# tl494.net
KiCad netlist of a schematic drawn in EAGLE
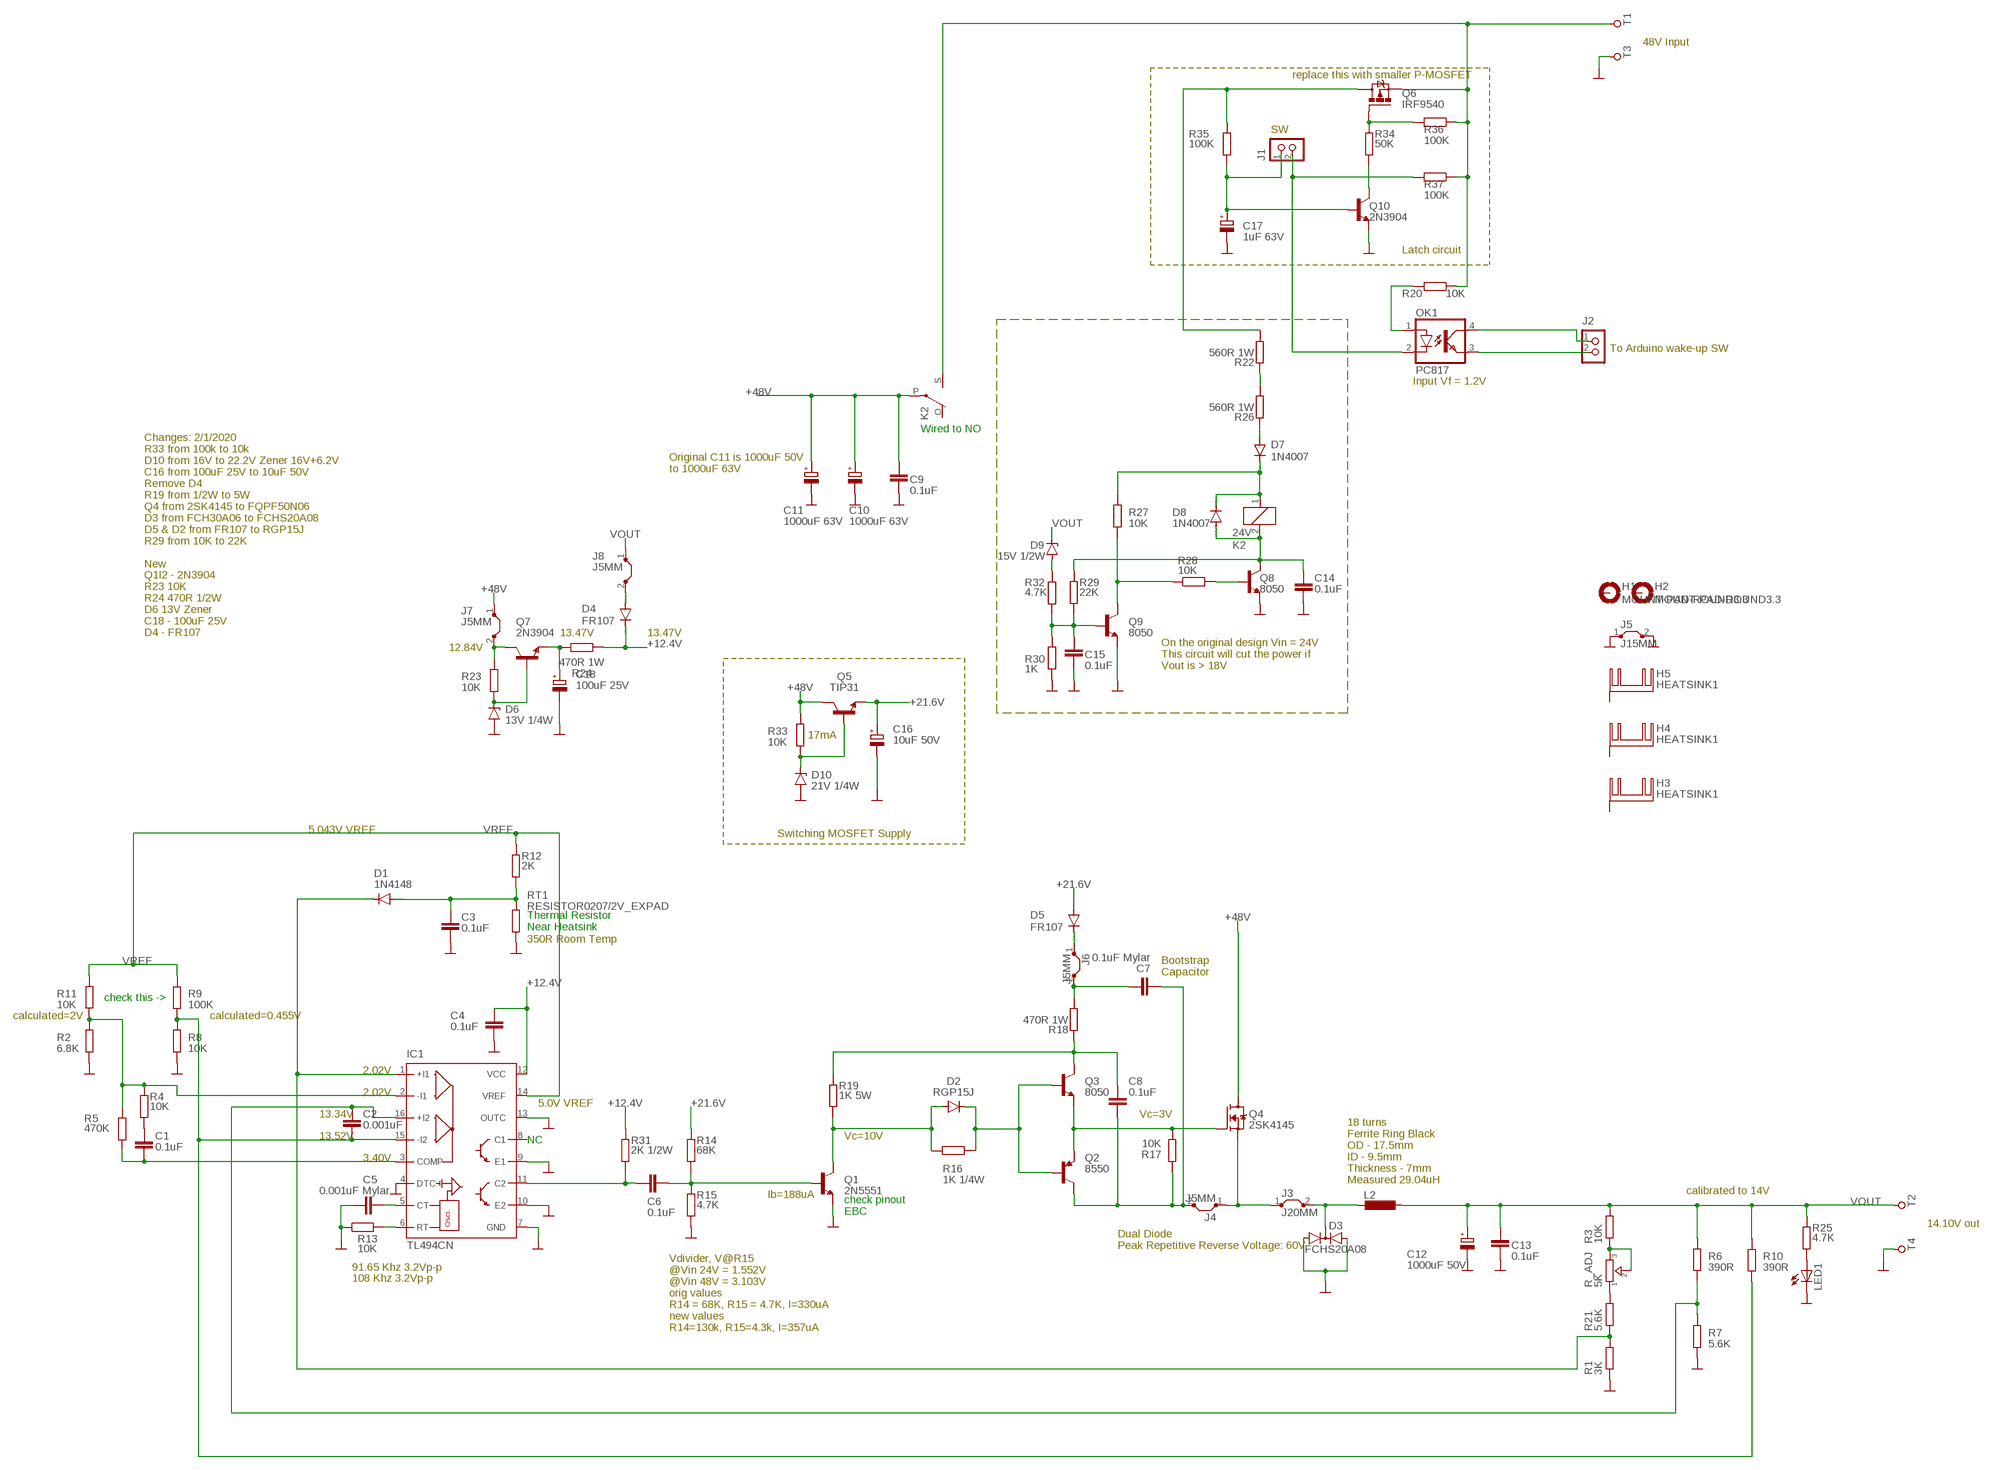
[diagram p0: schematic, sheet 1]

(export (version "E")
  (design (tool "Eeschema 10.0.6"))
  (components
    (comp (ref "C1")
      (value "0.1uF")
      (footprint "eagle-import:C050-024X044_EXPAD")
      (libsource (lib "eagle-import") (part "CAPACITORC050-024X044_EXPAD"))
    )
    (comp (ref "C2")
      (value "0.001uF")
      (footprint "eagle-import:C050-024X044_EXPAD")
      (libsource (lib "eagle-import") (part "CAPACITORC050-024X044_EXPAD"))
    )
    (comp (ref "C3")
      (value "0.1uF")
      (footprint "eagle-import:C050-024X044_EXPAD")
      (libsource (lib "eagle-import") (part "CAPACITORC050-024X044_EXPAD"))
    )
    (comp (ref "C4")
      (value "0.1uF")
      (footprint "eagle-import:C050-024X044_EXPAD")
      (libsource (lib "eagle-import") (part "CAPACITORC050-024X044_EXPAD"))
    )
    (comp (ref "C5")
      (value "0.001uF Mylar")
      (footprint "eagle-import:C050-024X044_EXPAD")
      (libsource (lib "eagle-import") (part "CAPACITORC050-024X044_EXPAD"))
    )
    (comp (ref "C6")
      (value "0.1uF")
      (footprint "eagle-import:C050-024X044_EXPAD")
      (libsource (lib "eagle-import") (part "CAPACITORC050-024X044_EXPAD"))
    )
    (comp (ref "C7")
      (value "0.1uF Mylar")
      (footprint "eagle-import:C050-050X075_EXPAD")
      (libsource (lib "eagle-import") (part "CAPACITORC050-050X075_EXPAD"))
    )
    (comp (ref "C8")
      (value "0.1uF")
      (footprint "eagle-import:C050-024X044_EXPAD")
      (libsource (lib "eagle-import") (part "CAPACITORC050-024X044_EXPAD"))
    )
    (comp (ref "C9")
      (value "0.1uF")
      (footprint "eagle-import:C050-024X044_EXPAD")
      (libsource (lib "eagle-import") (part "CAPACITORC050-024X044_EXPAD"))
    )
    (comp (ref "C10")
      (value "1000uF 63V")
      (footprint "eagle-import:E7,5-18")
      (libsource (lib "eagle-import") (part "CPOL-EUE7.5-18"))
    )
    (comp (ref "C11")
      (value "1000uF 63V")
      (footprint "eagle-import:E7,5-18")
      (libsource (lib "eagle-import") (part "CPOL-EUE7.5-18"))
    )
    (comp (ref "C12")
      (value "1000uF 50V")
      (footprint "eagle-import:E5-13")
      (libsource (lib "eagle-import") (part "CPOL-EUE5-13"))
    )
    (comp (ref "C13")
      (value "0.1uF")
      (footprint "eagle-import:C050-024X044_EXPAD")
      (libsource (lib "eagle-import") (part "CAPACITORC050-024X044_EXPAD"))
    )
    (comp (ref "C14")
      (value "0.1uF")
      (footprint "eagle-import:C050-024X044_EXPAD")
      (libsource (lib "eagle-import") (part "CAPACITORC050-024X044_EXPAD"))
    )
    (comp (ref "C15")
      (value "0.1uF")
      (footprint "eagle-import:C050-024X044_EXPAD")
      (libsource (lib "eagle-import") (part "CAPACITORC050-024X044_EXPAD"))
    )
    (comp (ref "C16")
      (value "10uF 50V")
      (footprint "eagle-import:E2,5-7_EXPAD")
      (libsource (lib "eagle-import") (part "CAPACITOR-POLE2,5-7_EXPAD"))
    )
    (comp (ref "C17")
      (value "1uF 63V")
      (footprint "eagle-import:E2-5_EXPAD")
      (libsource (lib "eagle-import") (part "CAPACITOR-POLE2,5_EXPAD"))
    )
    (comp (ref "C18")
      (value "100uF 25V")
      (footprint "eagle-import:E2,5-7_EXPAD")
      (libsource (lib "eagle-import") (part "CAPACITOR-POLE2,5-7_EXPAD"))
    )
    (comp (ref "D1")
      (value "1N4148")
      (footprint "eagle-import:DO35-10")
      (libsource (lib "eagle-import") (part "1N4148DO35-10"))
    )
    (comp (ref "D2")
      (value "RGP15J")
      (footprint "eagle-import:DO41-10")
      (libsource (lib "eagle-import") (part "1N4933"))
    )
    (comp (ref "D3")
      (value "FCHS20A08")
      (footprint "eagle-import:TO220ABS")
      (libsource (lib "eagle-import") (part "DIODE-2AC|CATO220V"))
    )
    (comp (ref "D4")
      (value "FR107")
      (footprint "eagle-import:DO41-10")
      (libsource (lib "eagle-import") (part "1N4933"))
    )
    (comp (ref "D5")
      (value "FR107")
      (footprint "eagle-import:DO41-10")
      (libsource (lib "eagle-import") (part "1N4933"))
    )
    (comp (ref "D6")
      (value "13V 1/4W")
      (footprint "eagle-import:DO34Z7")
      (libsource (lib "eagle-import") (part "BZV10"))
    )
    (comp (ref "D7")
      (value "1N4007")
      (footprint "eagle-import:DO41-10")
      (libsource (lib "eagle-import") (part "1N4933"))
    )
    (comp (ref "D8")
      (value "1N4007")
      (footprint "eagle-import:DO41-10")
      (libsource (lib "eagle-import") (part "1N4933"))
    )
    (comp (ref "D9")
      (value "15V 1/2W")
      (footprint "eagle-import:DO34Z7")
      (libsource (lib "eagle-import") (part "BZV10"))
    )
    (comp (ref "D10")
      (value "21V 1/4W")
      (footprint "eagle-import:DO34Z7")
      (libsource (lib "eagle-import") (part "BZV10"))
    )
    (comp (ref "H1")
      (value "MOUNT-PAD-ROUND3.3")
      (footprint "eagle-import:3,3-PAD")
      (libsource (lib "eagle-import") (part "MOUNT-PAD-ROUND3.3"))
    )
    (comp (ref "H2")
      (value "MOUNT-PAD-ROUND3.3")
      (footprint "eagle-import:3,3-PAD")
      (libsource (lib "eagle-import") (part "MOUNT-PAD-ROUND3.3"))
    )
    (comp (ref "H3")
      (value "HEATSINK1")
      (footprint "eagle-import:TO-220_HEATSINK1")
      (libsource (lib "eagle-import") (part "HEATSINK1"))
    )
    (comp (ref "H4")
      (value "HEATSINK1")
      (footprint "eagle-import:TO-220_HEATSINK1")
      (libsource (lib "eagle-import") (part "HEATSINK1"))
    )
    (comp (ref "H5")
      (value "HEATSINK1")
      (footprint "eagle-import:TO-220_HEATSINK1")
      (libsource (lib "eagle-import") (part "HEATSINK1"))
    )
    (comp (ref "IC1")
      (value "TL494CN")
      (footprint "eagle-import:DIL16")
      (libsource (lib "eagle-import") (part "TL494NC"))
    )
    (comp (ref "J1")
      (value "CON_HEADER_1X02-PTH")
      (footprint "eagle-import:M1X2")
      (libsource (lib "eagle-import") (part "CON_HEADER_1X02-PTH"))
    )
    (comp (ref "J2")
      (value "CON_HEADER_1X02-PTH")
      (footprint "eagle-import:M1X2")
      (libsource (lib "eagle-import") (part "CON_HEADER_1X02-PTH"))
    )
    (comp (ref "J3")
      (value "J20MM")
      (footprint "eagle-import:20")
      (libsource (lib "eagle-import") (part "J20MM"))
    )
    (comp (ref "J4")
      (value "J5MM")
      (footprint "eagle-import:05")
      (libsource (lib "eagle-import") (part "J5MM"))
    )
    (comp (ref "J5")
      (value "J15MM")
      (footprint "eagle-import:15")
      (libsource (lib "eagle-import") (part "J15MM"))
    )
    (comp (ref "J6")
      (value "J5MM")
      (footprint "eagle-import:05")
      (libsource (lib "eagle-import") (part "J5MM"))
    )
    (comp (ref "J7")
      (value "J5MM")
      (footprint "eagle-import:05")
      (libsource (lib "eagle-import") (part "J5MM"))
    )
    (comp (ref "J8")
      (value "J5MM")
      (footprint "eagle-import:05")
      (libsource (lib "eagle-import") (part "J5MM"))
    )
    (comp (ref "K2")
      (value "24V")
      (footprint "eagle-import:G5LE")
      (libsource (lib "eagle-import") (part "G5L"))
    )
    (comp (ref "L2")
      (value "L-EUTJ5-U1")
      (footprint "eagle-import:TJ5-U1")
      (libsource (lib "eagle-import") (part "L-EUTJ5-U1"))
    )
    (comp (ref "LED1")
      (value "LED-5MM")
      (footprint "eagle-import:LED-5MM")
      (libsource (lib "eagle-import") (part "LED-5MM"))
    )
    (comp (ref "OK1")
      (value "PC817")
      (footprint "eagle-import:DIL04")
      (fields (field (name "MPN") "PC817X4J000F"))
      (libsource (lib "eagle-import") (part "PC817"))
    )
    (comp (ref "Q1")
      (value "2N5551")
      (footprint "eagle-import:TO-92")
      (libsource (lib "eagle-import") (part "TRANSISTOR_BJT_NPN-TO-92-EBC"))
    )
    (comp (ref "Q2")
      (value "8550")
      (footprint "eagle-import:TO-92")
      (libsource (lib "eagle-import") (part "TRANSISTOR_BJT_PNP-TO-92-EBC"))
    )
    (comp (ref "Q3")
      (value "8050")
      (footprint "eagle-import:TO-92")
      (libsource (lib "eagle-import") (part "TRANSISTOR_BJT_NPN-TO-92-EBC"))
    )
    (comp (ref "Q4")
      (value "2SK4145")
      (footprint "eagle-import:TO-220V")
      (libsource (lib "eagle-import") (part "TRANSISTOR_MOSFET-N-TO220V"))
    )
    (comp (ref "Q5")
      (value "TIP31")
      (footprint "eagle-import:TO-220V")
      (libsource (lib "eagle-import") (part "Q_NPN_TIP31"))
    )
    (comp (ref "Q6")
      (value "IRF9540")
      (footprint "eagle-import:TO220BV")
      (libsource (lib "eagle-import") (part "IRF9530"))
    )
    (comp (ref "Q7")
      (value "2N3904")
      (footprint "eagle-import:TO-92")
      (libsource (lib "eagle-import") (part "TRANSISTOR_BJT_NPN-TO-92-EBC"))
    )
    (comp (ref "Q8")
      (value "8050")
      (footprint "eagle-import:TO-92")
      (libsource (lib "eagle-import") (part "TRANSISTOR_BJT_NPN-TO-92-EBC"))
    )
    (comp (ref "Q9")
      (value "8050")
      (footprint "eagle-import:TO-92")
      (libsource (lib "eagle-import") (part "TRANSISTOR_BJT_NPN-TO-92-EBC"))
    )
    (comp (ref "Q10")
      (value "2N3904")
      (footprint "eagle-import:TO-92")
      (libsource (lib "eagle-import") (part "TRANSISTOR_BJT_NPN-TO-92-EBC"))
    )
    (comp (ref "R1")
      (value "3K")
      (footprint "eagle-import:0207_10_EXPAD")
      (libsource (lib "eagle-import") (part "RESISTOR-0207/10_EXPAD"))
    )
    (comp (ref "R2")
      (value "6.8K")
      (footprint "eagle-import:0207_10_EXPAD")
      (libsource (lib "eagle-import") (part "RESISTOR-0207/10_EXPAD"))
    )
    (comp (ref "R3")
      (value "10K")
      (footprint "eagle-import:0207_10_EXPAD")
      (libsource (lib "eagle-import") (part "RESISTOR-0207/10_EXPAD"))
    )
    (comp (ref "R4")
      (value "10K")
      (footprint "eagle-import:0207_2V_EXPAD")
      (libsource (lib "eagle-import") (part "RESISTOR0207/2V_EXPAD"))
    )
    (comp (ref "R5")
      (value "470K")
      (footprint "eagle-import:0207_2V_EXPAD")
      (libsource (lib "eagle-import") (part "RESISTOR0207/2V_EXPAD"))
    )
    (comp (ref "R6")
      (value "390R")
      (footprint "eagle-import:0207_10_EXPAD")
      (libsource (lib "eagle-import") (part "RESISTOR-0207/10_EXPAD"))
    )
    (comp (ref "R7")
      (value "5.6K")
      (footprint "eagle-import:0207_2V_EXPAD")
      (libsource (lib "eagle-import") (part "RESISTOR0207/2V_EXPAD"))
    )
    (comp (ref "R8")
      (value "10K")
      (footprint "eagle-import:0207_2V_EXPAD")
      (libsource (lib "eagle-import") (part "RESISTOR0207/2V_EXPAD"))
    )
    (comp (ref "R9")
      (value "100K")
      (footprint "eagle-import:0207_10_EXPAD")
      (libsource (lib "eagle-import") (part "RESISTOR-0207/10_EXPAD"))
    )
    (comp (ref "R10")
      (value "390R")
      (footprint "eagle-import:0207_10_EXPAD")
      (libsource (lib "eagle-import") (part "RESISTOR-0207/10_EXPAD"))
    )
    (comp (ref "R11")
      (value "10K")
      (footprint "eagle-import:0207_10_EXPAD")
      (libsource (lib "eagle-import") (part "RESISTOR-0207/10_EXPAD"))
    )
    (comp (ref "R12")
      (value "2K")
      (footprint "eagle-import:0207_10_EXPAD")
      (libsource (lib "eagle-import") (part "RESISTOR-0207/10_EXPAD"))
    )
    (comp (ref "R13")
      (value "10K")
      (footprint "eagle-import:0207_2V_EXPAD")
      (libsource (lib "eagle-import") (part "RESISTOR0207/2V_EXPAD"))
    )
    (comp (ref "R14")
      (value "68K")
      (footprint "eagle-import:0207_2V_EXPAD")
      (libsource (lib "eagle-import") (part "RESISTOR0207/2V_EXPAD"))
    )
    (comp (ref "R15")
      (value "4.7K")
      (footprint "eagle-import:0207_2V_EXPAD")
      (libsource (lib "eagle-import") (part "RESISTOR0207/2V_EXPAD"))
    )
    (comp (ref "R16")
      (value "1K 1/4W")
      (footprint "eagle-import:0207_10_EXPAD")
      (libsource (lib "eagle-import") (part "RESISTOR-0207/10_EXPAD"))
    )
    (comp (ref "R17")
      (value "10K")
      (footprint "eagle-import:0207_2V_EXPAD")
      (libsource (lib "eagle-import") (part "RESISTOR0207/2V_EXPAD"))
    )
    (comp (ref "R18")
      (value "470R 1W")
      (footprint "eagle-import:0414V_EXPAD")
      (libsource (lib "eagle-import") (part "RESISTOR0414V_EXPAD"))
    )
    (comp (ref "R19")
      (value "1K 5W")
      (footprint "eagle-import:0414V_EXPAD")
      (libsource (lib "eagle-import") (part "RESISTOR0414V_EXPAD"))
    )
    (comp (ref "R20")
      (value "10K")
      (footprint "eagle-import:0207_10_EXPAD")
      (libsource (lib "eagle-import") (part "RESISTOR-0207/10_EXPAD"))
    )
    (comp (ref "R21")
      (value "5.6K")
      (footprint "eagle-import:0207_2V_EXPAD")
      (libsource (lib "eagle-import") (part "RESISTOR0207/2V_EXPAD"))
    )
    (comp (ref "R22")
      (value "560R 1W")
      (footprint "eagle-import:0414V_EXPAD")
      (libsource (lib "eagle-import") (part "RESISTOR0414V_EXPAD"))
    )
    (comp (ref "R23")
      (value "10K")
      (footprint "eagle-import:0207_2V_EXPAD")
      (libsource (lib "eagle-import") (part "RESISTOR0207/2V_EXPAD"))
    )
    (comp (ref "R24")
      (value "470R 1W")
      (footprint "eagle-import:0414V_EXPAD")
      (libsource (lib "eagle-import") (part "RESISTOR0414V_EXPAD"))
    )
    (comp (ref "R25")
      (value "4.7K")
      (footprint "eagle-import:0207_10_EXPAD")
      (libsource (lib "eagle-import") (part "RESISTOR-0207/10_EXPAD"))
    )
    (comp (ref "R26")
      (value "560R 1W")
      (footprint "eagle-import:0414V_EXPAD")
      (libsource (lib "eagle-import") (part "RESISTOR0414V_EXPAD"))
    )
    (comp (ref "R27")
      (value "10K")
      (footprint "eagle-import:0207_10_EXPAD")
      (libsource (lib "eagle-import") (part "RESISTOR-0207/10_EXPAD"))
    )
    (comp (ref "R28")
      (value "10K")
      (footprint "eagle-import:0207_10_EXPAD")
      (libsource (lib "eagle-import") (part "RESISTOR-0207/10_EXPAD"))
    )
    (comp (ref "R29")
      (value "22K")
      (footprint "eagle-import:0207_10_EXPAD")
      (libsource (lib "eagle-import") (part "RESISTOR-0207/10_EXPAD"))
    )
    (comp (ref "R30")
      (value "1K")
      (footprint "eagle-import:0207_2V_EXPAD")
      (libsource (lib "eagle-import") (part "RESISTOR0207/2V_EXPAD"))
    )
    (comp (ref "R31")
      (value "2K 1/2W")
      (footprint "eagle-import:0207_2V_EXPAD")
      (libsource (lib "eagle-import") (part "RESISTOR0207/2V_EXPAD"))
    )
    (comp (ref "R32")
      (value "4.7K")
      (footprint "eagle-import:0207_2V_EXPAD")
      (libsource (lib "eagle-import") (part "RESISTOR0207/2V_EXPAD"))
    )
    (comp (ref "R33")
      (value "10K")
      (footprint "eagle-import:0207_2V_EXPAD")
      (libsource (lib "eagle-import") (part "RESISTOR0207/2V_EXPAD"))
    )
    (comp (ref "R34")
      (value "50K")
      (footprint "eagle-import:0207_2V_EXPAD")
      (libsource (lib "eagle-import") (part "RESISTOR0207/2V_EXPAD"))
    )
    (comp (ref "R35")
      (value "100K")
      (footprint "eagle-import:0207_2V_EXPAD")
      (libsource (lib "eagle-import") (part "RESISTOR0207/2V_EXPAD"))
    )
    (comp (ref "R36")
      (value "100K")
      (footprint "eagle-import:0207_2V")
      (libsource (lib "eagle-import") (part "R-EU_0207/2V"))
    )
    (comp (ref "R37")
      (value "100K")
      (footprint "eagle-import:0207_10")
      (libsource (lib "eagle-import") (part "R-EU_0207/10"))
    )
    (comp (ref "RT1")
      (value "RESISTOR0207/2V_EXPAD")
      (footprint "eagle-import:0207_2V_EXPAD")
      (libsource (lib "eagle-import") (part "RESISTOR0207/2V_EXPAD"))
    )
    (comp (ref "R_ADJ")
      (value "5K")
      (footprint "eagle-import:TRIMMER_3362P_EXPAD")
      (libsource (lib "eagle-import") (part "TRIMMER-3362P_EXPAD"))
    )
    (comp (ref "T1")
      (value "PAD_TERMINAL-1.02MM_ROUND")
      (footprint "eagle-import:CON_PAD_ROUND_1.02MM")
      (libsource (lib "eagle-import") (part "PAD_TERMINAL-1.02MM_ROUND"))
    )
    (comp (ref "T2")
      (value "PAD_TERMINAL-1.02MM_ROUND")
      (footprint "eagle-import:CON_PAD_ROUND_1.02MM")
      (libsource (lib "eagle-import") (part "PAD_TERMINAL-1.02MM_ROUND"))
    )
    (comp (ref "T3")
      (value "PAD_TERMINAL-1.02MM_SQUARE")
      (footprint "eagle-import:CON_PAD_SQUARE_1.02MM")
      (libsource (lib "eagle-import") (part "PAD_TERMINAL-1.02MM_SQUARE"))
    )
    (comp (ref "T4")
      (value "PAD_TERMINAL-1.02MM_ROUND")
      (footprint "eagle-import:CON_PAD_ROUND_1.02MM")
      (libsource (lib "eagle-import") (part "PAD_TERMINAL-1.02MM_ROUND"))
    )
  )
  (nets
    (net (code "1") (name "/+12.4V") (class "Default")
      (node (ref "C4") (pin "2") (pinfunction "2_2") (pintype "passive"))
      (node (ref "D4") (pin "C") (pinfunction "C_C") (pintype "passive"))
      (node (ref "IC1") (pin "12") (pinfunction "VCC_12") (pintype "power_in"))
      (node (ref "R24") (pin "1") (pinfunction "1_1") (pintype "passive"))
      (node (ref "R31") (pin "2") (pinfunction "2_2") (pintype "passive"))
    )
    (net (code "2") (name "/+21.6V") (class "Default")
      (node (ref "C16") (pin "+") (pinfunction "+_+") (pintype "passive"))
      (node (ref "D5") (pin "A") (pinfunction "A_A") (pintype "passive"))
      (node (ref "Q5") (pin "3") (pinfunction "E_3") (pintype "passive"))
      (node (ref "R14") (pin "2") (pinfunction "2_2") (pintype "passive"))
    )
    (net (code "3") (name "/+48V") (class "Default")
      (node (ref "C10") (pin "+") (pinfunction "+_+") (pintype "passive"))
      (node (ref "C11") (pin "+") (pinfunction "+_+") (pintype "passive"))
      (node (ref "C9") (pin "1") (pinfunction "1_1") (pintype "passive"))
      (node (ref "J7") (pin "1") (pinfunction "1_1") (pintype "passive"))
      (node (ref "K2") (pin "P") (pinfunction "P_P") (pintype "passive"))
      (node (ref "Q4") (pin "2") (pinfunction "D_2") (pintype "passive"))
      (node (ref "Q5") (pin "2") (pinfunction "C_2") (pintype "passive"))
      (node (ref "R33") (pin "1") (pinfunction "1_1") (pintype "passive"))
    )
    (net (code "4") (name "/VOUT") (class "Default")
      (node (ref "C12") (pin "+") (pinfunction "+_+") (pintype "passive"))
      (node (ref "C13") (pin "1") (pinfunction "1_1") (pintype "passive"))
      (node (ref "D9") (pin "C") (pinfunction "C_C") (pintype "passive"))
      (node (ref "J8") (pin "1") (pinfunction "1_1") (pintype "passive"))
      (node (ref "L2") (pin "1") (pinfunction "1_1") (pintype "passive"))
      (node (ref "R10") (pin "1") (pinfunction "1_1") (pintype "passive"))
      (node (ref "R25") (pin "2") (pinfunction "2_2") (pintype "passive"))
      (node (ref "R3") (pin "2") (pinfunction "2_2") (pintype "passive"))
      (node (ref "R6") (pin "2") (pinfunction "2_2") (pintype "passive"))
      (node (ref "T2") (pin "P") (pinfunction "P_P") (pintype "passive"))
    )
    (net (code "5") (name "/VREF") (class "Default")
      (node (ref "IC1") (pin "14") (pinfunction "VREF_14") (pintype "input"))
      (node (ref "R11") (pin "2") (pinfunction "2_2") (pintype "passive"))
      (node (ref "R12") (pin "2") (pinfunction "2_2") (pintype "passive"))
      (node (ref "R9") (pin "1") (pinfunction "1_1") (pintype "passive"))
    )
    (net (code "6") (name "Net-(C1-Pad2)") (class "Default")
      (node (ref "C1") (pin "2") (pinfunction "2_2") (pintype "passive"))
      (node (ref "R4") (pin "1") (pinfunction "1_1") (pintype "passive"))
    )
    (net (code "7") (name "Net-(C3-Pad2)") (class "Default")
      (node (ref "C3") (pin "2") (pinfunction "2_2") (pintype "passive"))
      (node (ref "D1") (pin "A") (pinfunction "A_A") (pintype "passive"))
      (node (ref "R12") (pin "1") (pinfunction "1_1") (pintype "passive"))
      (node (ref "RT1") (pin "1") (pinfunction "1_1") (pintype "passive"))
    )
    (net (code "8") (name "Net-(C7-Pad1)") (class "Default")
      (node (ref "C7") (pin "1") (pinfunction "1_1") (pintype "passive"))
      (node (ref "J6") (pin "2") (pinfunction "2_2") (pintype "passive"))
      (node (ref "R18") (pin "1") (pinfunction "1_1") (pintype "passive"))
    )
    (net (code "9") (name "Net-(D3-PadC)") (class "Default")
      (node (ref "D3") (pin "C") (pinfunction "C_C") (pintype "passive"))
      (node (ref "J3") (pin "2") (pinfunction "2_2") (pintype "passive"))
      (node (ref "L2") (pin "2") (pinfunction "2_2") (pintype "passive"))
    )
    (net (code "10") (name "Net-(D4-PadA)") (class "Default")
      (node (ref "D4") (pin "A") (pinfunction "A_A") (pintype "passive"))
      (node (ref "J8") (pin "2") (pinfunction "2_2") (pintype "passive"))
    )
    (net (code "11") (name "Net-(D5-PadC)") (class "Default")
      (node (ref "D5") (pin "C") (pinfunction "C_C") (pintype "passive"))
      (node (ref "J6") (pin "1") (pinfunction "1_1") (pintype "passive"))
    )
    (net (code "12") (name "Net-(D7-PadA)") (class "Default")
      (node (ref "D7") (pin "A") (pinfunction "A_A") (pintype "passive"))
      (node (ref "R26") (pin "2") (pinfunction "2_2") (pintype "passive"))
    )
    (net (code "13") (name "Net-(D7-PadC)") (class "Default")
      (node (ref "D7") (pin "C") (pinfunction "C_C") (pintype "passive"))
      (node (ref "D8") (pin "C") (pinfunction "C_C") (pintype "passive"))
      (node (ref "K2") (pin "1") (pinfunction "1_1") (pintype "passive"))
      (node (ref "R27") (pin "2") (pinfunction "2_2") (pintype "passive"))
    )
    (net (code "14") (name "Net-(D9-PadA)") (class "Default")
      (node (ref "D9") (pin "A") (pinfunction "A_A") (pintype "passive"))
      (node (ref "R32") (pin "1") (pinfunction "1_1") (pintype "passive"))
    )
    (net (code "15") (name "Net-(IC1-+I1)") (class "Default")
      (node (ref "D1") (pin "C") (pinfunction "C_C") (pintype "passive"))
      (node (ref "IC1") (pin "1") (pinfunction "+I1_1") (pintype "input"))
      (node (ref "R1") (pin "2") (pinfunction "2_2") (pintype "passive"))
      (node (ref "R21") (pin "1") (pinfunction "1_1") (pintype "passive"))
    )
    (net (code "16") (name "Net-(IC1-+I2)") (class "Default")
      (node (ref "C2") (pin "2") (pinfunction "2_2") (pintype "passive"))
      (node (ref "IC1") (pin "16") (pinfunction "+I2_16") (pintype "input"))
      (node (ref "R6") (pin "1") (pinfunction "1_1") (pintype "passive"))
      (node (ref "R7") (pin "2") (pinfunction "2_2") (pintype "passive"))
    )
    (net (code "17") (name "Net-(IC1--I1)") (class "Default")
      (node (ref "IC1") (pin "2") (pinfunction "-I1_2") (pintype "input"))
      (node (ref "R11") (pin "1") (pinfunction "1_1") (pintype "passive"))
      (node (ref "R2") (pin "2") (pinfunction "2_2") (pintype "passive"))
      (node (ref "R4") (pin "2") (pinfunction "2_2") (pintype "passive"))
      (node (ref "R5") (pin "1") (pinfunction "1_1") (pintype "passive"))
    )
    (net (code "18") (name "Net-(IC1--I2)") (class "Default")
      (node (ref "C2") (pin "1") (pinfunction "1_1") (pintype "passive"))
      (node (ref "IC1") (pin "15") (pinfunction "-I2_15") (pintype "input"))
      (node (ref "R10") (pin "2") (pinfunction "2_2") (pintype "passive"))
      (node (ref "R8") (pin "2") (pinfunction "2_2") (pintype "passive"))
      (node (ref "R9") (pin "2") (pinfunction "2_2") (pintype "passive"))
    )
    (net (code "19") (name "Net-(IC1-C2)") (class "Default")
      (node (ref "C6") (pin "2") (pinfunction "2_2") (pintype "passive"))
      (node (ref "IC1") (pin "11") (pinfunction "C2_11") (pintype "passive"))
      (node (ref "R31") (pin "1") (pinfunction "1_1") (pintype "passive"))
    )
    (net (code "20") (name "Net-(IC1-COMP)") (class "Default")
      (node (ref "C1") (pin "1") (pinfunction "1_1") (pintype "passive"))
      (node (ref "IC1") (pin "3") (pinfunction "COMP_3") (pintype "passive"))
      (node (ref "R5") (pin "2") (pinfunction "2_2") (pintype "passive"))
    )
    (net (code "21") (name "Net-(IC1-CT)") (class "Default")
      (node (ref "C5") (pin "1") (pinfunction "1_1") (pintype "passive"))
      (node (ref "IC1") (pin "5") (pinfunction "CT_5") (pintype "input"))
    )
    (net (code "22") (name "Net-(IC1-RT)") (class "Default")
      (node (ref "IC1") (pin "6") (pinfunction "RT_6") (pintype "input"))
      (node (ref "R13") (pin "2") (pinfunction "2_2") (pintype "passive"))
    )
    (net (code "23") (name "Net-(K2-PadS)") (class "Default")
      (node (ref "K2") (pin "S") (pinfunction "S_S") (pintype "passive"))
      (node (ref "Q6") (pin "S") (pinfunction "S_S") (pintype "passive"))
      (node (ref "R20") (pin "1") (pinfunction "1_1") (pintype "passive"))
      (node (ref "R36") (pin "1") (pinfunction "1_1") (pintype "passive"))
      (node (ref "R37") (pin "1") (pinfunction "1_1") (pintype "passive"))
      (node (ref "T1") (pin "P") (pinfunction "P_P") (pintype "passive"))
    )
    (net (code "24") (name "Net-(LED1-PadA)") (class "Default")
      (node (ref "LED1") (pin "A") (pinfunction "A_A") (pintype "passive"))
      (node (ref "R25") (pin "1") (pinfunction "1_1") (pintype "passive"))
    )
    (net (code "25") (name "Net-(OK1-A)") (class "Default")
      (node (ref "OK1") (pin "1") (pinfunction "A_1") (pintype "passive"))
      (node (ref "R20") (pin "2") (pinfunction "2_2") (pintype "passive"))
    )
    (net (code "26") (name "Net-(OK1-C)") (class "Default")
      (node (ref "J1") (pin "2") (pinfunction "2_2") (pintype "passive"))
      (node (ref "OK1") (pin "2") (pinfunction "C_2") (pintype "passive"))
      (node (ref "R37") (pin "2") (pinfunction "2_2") (pintype "passive"))
    )
    (net (code "27") (name "Net-(OK1-COL)") (class "Default")
      (node (ref "J2") (pin "1") (pinfunction "1_1") (pintype "passive"))
      (node (ref "OK1") (pin "4") (pinfunction "COL_4") (pintype "passive"))
    )
    (net (code "28") (name "Net-(OK1-EMIT)") (class "Default")
      (node (ref "J2") (pin "2") (pinfunction "2_2") (pintype "passive"))
      (node (ref "OK1") (pin "3") (pinfunction "EMIT_3") (pintype "passive"))
    )
    (net (code "29") (name "Net-(Q1-B)") (class "Default")
      (node (ref "C6") (pin "1") (pinfunction "1_1") (pintype "passive"))
      (node (ref "Q1") (pin "2") (pinfunction "B_2") (pintype "passive"))
      (node (ref "R14") (pin "1") (pinfunction "1_1") (pintype "passive"))
      (node (ref "R15") (pin "2") (pinfunction "2_2") (pintype "passive"))
    )
    (net (code "30") (name "Net-(Q1-C)") (class "Default")
      (node (ref "D2") (pin "A") (pinfunction "A_A") (pintype "passive"))
      (node (ref "Q1") (pin "3") (pinfunction "C_3") (pintype "passive"))
      (node (ref "R16") (pin "1") (pinfunction "1_1") (pintype "passive"))
      (node (ref "R19") (pin "1") (pinfunction "1_1") (pintype "passive"))
    )
    (net (code "31") (name "Net-(Q2-B)") (class "Default")
      (node (ref "D2") (pin "C") (pinfunction "C_C") (pintype "passive"))
      (node (ref "Q2") (pin "2") (pinfunction "B_2") (pintype "passive"))
      (node (ref "Q3") (pin "2") (pinfunction "B_2") (pintype "passive"))
      (node (ref "R16") (pin "2") (pinfunction "2_2") (pintype "passive"))
    )
    (net (code "32") (name "Net-(Q2-C)") (class "Default")
      (node (ref "C7") (pin "2") (pinfunction "2_2") (pintype "passive"))
      (node (ref "C8") (pin "2") (pinfunction "2_2") (pintype "passive"))
      (node (ref "J4") (pin "2") (pinfunction "2_2") (pintype "passive"))
      (node (ref "Q2") (pin "3") (pinfunction "C_3") (pintype "passive"))
      (node (ref "R17") (pin "1") (pinfunction "1_1") (pintype "passive"))
    )
    (net (code "33") (name "Net-(Q2-E)") (class "Default")
      (node (ref "Q2") (pin "1") (pinfunction "E_1") (pintype "passive"))
      (node (ref "Q3") (pin "1") (pinfunction "E_1") (pintype "passive"))
      (node (ref "Q4") (pin "1") (pinfunction "G_1") (pintype "passive"))
      (node (ref "R17") (pin "2") (pinfunction "2_2") (pintype "passive"))
    )
    (net (code "34") (name "Net-(Q3-C)") (class "Default")
      (node (ref "C8") (pin "1") (pinfunction "1_1") (pintype "passive"))
      (node (ref "Q3") (pin "3") (pinfunction "C_3") (pintype "passive"))
      (node (ref "R18") (pin "2") (pinfunction "2_2") (pintype "passive"))
      (node (ref "R19") (pin "2") (pinfunction "2_2") (pintype "passive"))
    )
    (net (code "35") (name "Net-(Q4-S)") (class "Default")
      (node (ref "J3") (pin "1") (pinfunction "1_1") (pintype "passive"))
      (node (ref "J4") (pin "1") (pinfunction "1_1") (pintype "passive"))
      (node (ref "Q4") (pin "3") (pinfunction "S_3") (pintype "passive"))
    )
    (net (code "36") (name "Net-(Q5-B)") (class "Default")
      (node (ref "D10") (pin "C") (pinfunction "C_C") (pintype "passive"))
      (node (ref "Q5") (pin "1") (pinfunction "B_1") (pintype "passive"))
      (node (ref "R33") (pin "2") (pinfunction "2_2") (pintype "passive"))
    )
    (net (code "37") (name "Net-(Q6-PadD)") (class "Default")
      (node (ref "Q6") (pin "D") (pinfunction "D_D") (pintype "passive"))
      (node (ref "R22") (pin "1") (pinfunction "1_1") (pintype "passive"))
      (node (ref "R35") (pin "2") (pinfunction "2_2") (pintype "passive"))
    )
    (net (code "38") (name "Net-(Q6-PadG)") (class "Default")
      (node (ref "Q6") (pin "G") (pinfunction "G_G") (pintype "passive"))
      (node (ref "R34") (pin "2") (pinfunction "2_2") (pintype "passive"))
      (node (ref "R36") (pin "2") (pinfunction "2_2") (pintype "passive"))
    )
    (net (code "39") (name "Net-(Q7-B)") (class "Default")
      (node (ref "D6") (pin "C") (pinfunction "C_C") (pintype "passive"))
      (node (ref "Q7") (pin "2") (pinfunction "B_2") (pintype "passive"))
      (node (ref "R23") (pin "2") (pinfunction "2_2") (pintype "passive"))
    )
    (net (code "40") (name "Net-(Q7-C)") (class "Default")
      (node (ref "J7") (pin "2") (pinfunction "2_2") (pintype "passive"))
      (node (ref "Q7") (pin "3") (pinfunction "C_3") (pintype "passive"))
      (node (ref "R23") (pin "1") (pinfunction "1_1") (pintype "passive"))
    )
    (net (code "41") (name "Net-(Q7-E)") (class "Default")
      (node (ref "C18") (pin "+") (pinfunction "+_+") (pintype "passive"))
      (node (ref "Q7") (pin "1") (pinfunction "E_1") (pintype "passive"))
      (node (ref "R24") (pin "2") (pinfunction "2_2") (pintype "passive"))
    )
    (net (code "42") (name "Net-(Q8-B)") (class "Default")
      (node (ref "Q8") (pin "2") (pinfunction "B_2") (pintype "passive"))
      (node (ref "R28") (pin "2") (pinfunction "2_2") (pintype "passive"))
    )
    (net (code "43") (name "Net-(Q8-C)") (class "Default")
      (node (ref "C14") (pin "1") (pinfunction "1_1") (pintype "passive"))
      (node (ref "D8") (pin "A") (pinfunction "A_A") (pintype "passive"))
      (node (ref "K2") (pin "2") (pinfunction "2_2") (pintype "passive"))
      (node (ref "Q8") (pin "3") (pinfunction "C_3") (pintype "passive"))
      (node (ref "R29") (pin "2") (pinfunction "2_2") (pintype "passive"))
    )
    (net (code "44") (name "Net-(Q9-B)") (class "Default")
      (node (ref "C15") (pin "1") (pinfunction "1_1") (pintype "passive"))
      (node (ref "Q9") (pin "2") (pinfunction "B_2") (pintype "passive"))
      (node (ref "R29") (pin "1") (pinfunction "1_1") (pintype "passive"))
      (node (ref "R30") (pin "2") (pinfunction "2_2") (pintype "passive"))
      (node (ref "R32") (pin "2") (pinfunction "2_2") (pintype "passive"))
    )
    (net (code "45") (name "Net-(Q9-C)") (class "Default")
      (node (ref "Q9") (pin "3") (pinfunction "C_3") (pintype "passive"))
      (node (ref "R27") (pin "1") (pinfunction "1_1") (pintype "passive"))
      (node (ref "R28") (pin "1") (pinfunction "1_1") (pintype "passive"))
    )
    (net (code "46") (name "Net-(Q10-B)") (class "Default")
      (node (ref "C17") (pin "+") (pinfunction "+_+") (pintype "passive"))
      (node (ref "J1") (pin "1") (pinfunction "1_1") (pintype "passive"))
      (node (ref "Q10") (pin "2") (pinfunction "B_2") (pintype "passive"))
      (node (ref "R35") (pin "1") (pinfunction "1_1") (pintype "passive"))
    )
    (net (code "47") (name "Net-(Q10-C)") (class "Default")
      (node (ref "Q10") (pin "3") (pinfunction "C_3") (pintype "passive"))
      (node (ref "R34") (pin "1") (pinfunction "1_1") (pintype "passive"))
    )
    (net (code "48") (name "Net-(R3-Pad1)") (class "Default")
      (node (ref "R3") (pin "1") (pinfunction "1_1") (pintype "passive"))
      (node (ref "R_ADJ") (pin "2") (pinfunction "2_2") (pintype "passive"))
      (node (ref "R_ADJ") (pin "3") (pinfunction "3_3") (pintype "passive"))
    )
    (net (code "49") (name "Net-(R21-Pad2)") (class "Default")
      (node (ref "R21") (pin "2") (pinfunction "2_2") (pintype "passive"))
      (node (ref "R_ADJ") (pin "1") (pinfunction "1_1") (pintype "passive"))
    )
    (net (code "50") (name "Net-(R22-Pad2)") (class "Default")
      (node (ref "R22") (pin "2") (pinfunction "2_2") (pintype "passive"))
      (node (ref "R26") (pin "1") (pinfunction "1_1") (pintype "passive"))
    )
    (net (code "51") (name "SUPPLY_GND") (class "Default")
      (node (ref "C10") (pin "-") (pinfunction "-_-") (pintype "passive"))
      (node (ref "C11") (pin "-") (pinfunction "-_-") (pintype "passive"))
      (node (ref "C12") (pin "-") (pinfunction "-_-") (pintype "passive"))
      (node (ref "C13") (pin "2") (pinfunction "2_2") (pintype "passive"))
      (node (ref "C14") (pin "2") (pinfunction "2_2") (pintype "passive"))
      (node (ref "C15") (pin "2") (pinfunction "2_2") (pintype "passive"))
      (node (ref "C16") (pin "-") (pinfunction "-_-") (pintype "passive"))
      (node (ref "C17") (pin "-") (pinfunction "-_-") (pintype "passive"))
      (node (ref "C18") (pin "-") (pinfunction "-_-") (pintype "passive"))
      (node (ref "C3") (pin "1") (pinfunction "1_1") (pintype "passive"))
      (node (ref "C4") (pin "1") (pinfunction "1_1") (pintype "passive"))
      (node (ref "C5") (pin "2") (pinfunction "2_2") (pintype "passive"))
      (node (ref "C9") (pin "2") (pinfunction "2_2") (pintype "passive"))
      (node (ref "D10") (pin "A") (pinfunction "A_A") (pintype "passive"))
      (node (ref "D3") (pin "A1") (pinfunction "A1_A1") (pintype "passive"))
      (node (ref "D3") (pin "A2") (pinfunction "A2_A2") (pintype "passive"))
      (node (ref "D6") (pin "A") (pinfunction "A_A") (pintype "passive"))
      (node (ref "IC1") (pin "10") (pinfunction "E2_10") (pintype "passive"))
      (node (ref "IC1") (pin "13") (pinfunction "OUTC_13") (pintype "output"))
      (node (ref "IC1") (pin "4") (pinfunction "DTC_4") (pintype "input"))
      (node (ref "IC1") (pin "7") (pinfunction "GND_7") (pintype "power_in"))
      (node (ref "IC1") (pin "9") (pinfunction "E1_9") (pintype "passive"))
      (node (ref "J5") (pin "1") (pinfunction "1_1") (pintype "passive"))
      (node (ref "J5") (pin "2") (pinfunction "2_2") (pintype "passive"))
      (node (ref "LED1") (pin "K") (pinfunction "C_K") (pintype "passive"))
      (node (ref "Q1") (pin "1") (pinfunction "E_1") (pintype "passive"))
      (node (ref "Q10") (pin "1") (pinfunction "E_1") (pintype "passive"))
      (node (ref "Q8") (pin "1") (pinfunction "E_1") (pintype "passive"))
      (node (ref "Q9") (pin "1") (pinfunction "E_1") (pintype "passive"))
      (node (ref "R1") (pin "1") (pinfunction "1_1") (pintype "passive"))
      (node (ref "R13") (pin "1") (pinfunction "1_1") (pintype "passive"))
      (node (ref "R15") (pin "1") (pinfunction "1_1") (pintype "passive"))
      (node (ref "R2") (pin "1") (pinfunction "1_1") (pintype "passive"))
      (node (ref "R30") (pin "1") (pinfunction "1_1") (pintype "passive"))
      (node (ref "R7") (pin "1") (pinfunction "1_1") (pintype "passive"))
      (node (ref "R8") (pin "1") (pinfunction "1_1") (pintype "passive"))
      (node (ref "RT1") (pin "2") (pinfunction "2_2") (pintype "passive"))
      (node (ref "T3") (pin "P") (pinfunction "P_P") (pintype "passive"))
      (node (ref "T4") (pin "P") (pinfunction "P_P") (pintype "passive"))
    )
    (net (code "52") (name "unconnected-(H1-MOUNT-PadB3,3)") (class "Default")
      (node (ref "H1") (pin "B3,3") (pinfunction "MOUNT_B3,3") (pintype "passive"))
    )
    (net (code "53") (name "unconnected-(H2-MOUNT-PadB3,3)") (class "Default")
      (node (ref "H2") (pin "B3,3") (pinfunction "MOUNT_B3,3") (pintype "passive"))
    )
    (net (code "54") (name "unconnected-(H3-K-Pad1)") (class "Default")
      (node (ref "H3") (pin "1") (pinfunction "K_1") (pintype "passive"))
    )
    (net (code "55") (name "unconnected-(H4-K-Pad1)") (class "Default")
      (node (ref "H4") (pin "1") (pinfunction "K_1") (pintype "passive"))
    )
    (net (code "56") (name "unconnected-(H5-K-Pad1)") (class "Default")
      (node (ref "H5") (pin "1") (pinfunction "K_1") (pintype "passive"))
    )
    (net (code "57") (name "unconnected-(IC1-C1-Pad8)") (class "Default")
      (node (ref "IC1") (pin "8") (pinfunction "C1_8") (pintype "passive"))
    )
    (net (code "58") (name "unconnected-(K2-PadO)") (class "Default")
      (node (ref "K2") (pin "O") (pinfunction "O_O") (pintype "passive"))
    )
  )
)
